# Sheet1.net
KiCad netlist of a schematic drawn in Altium Designer
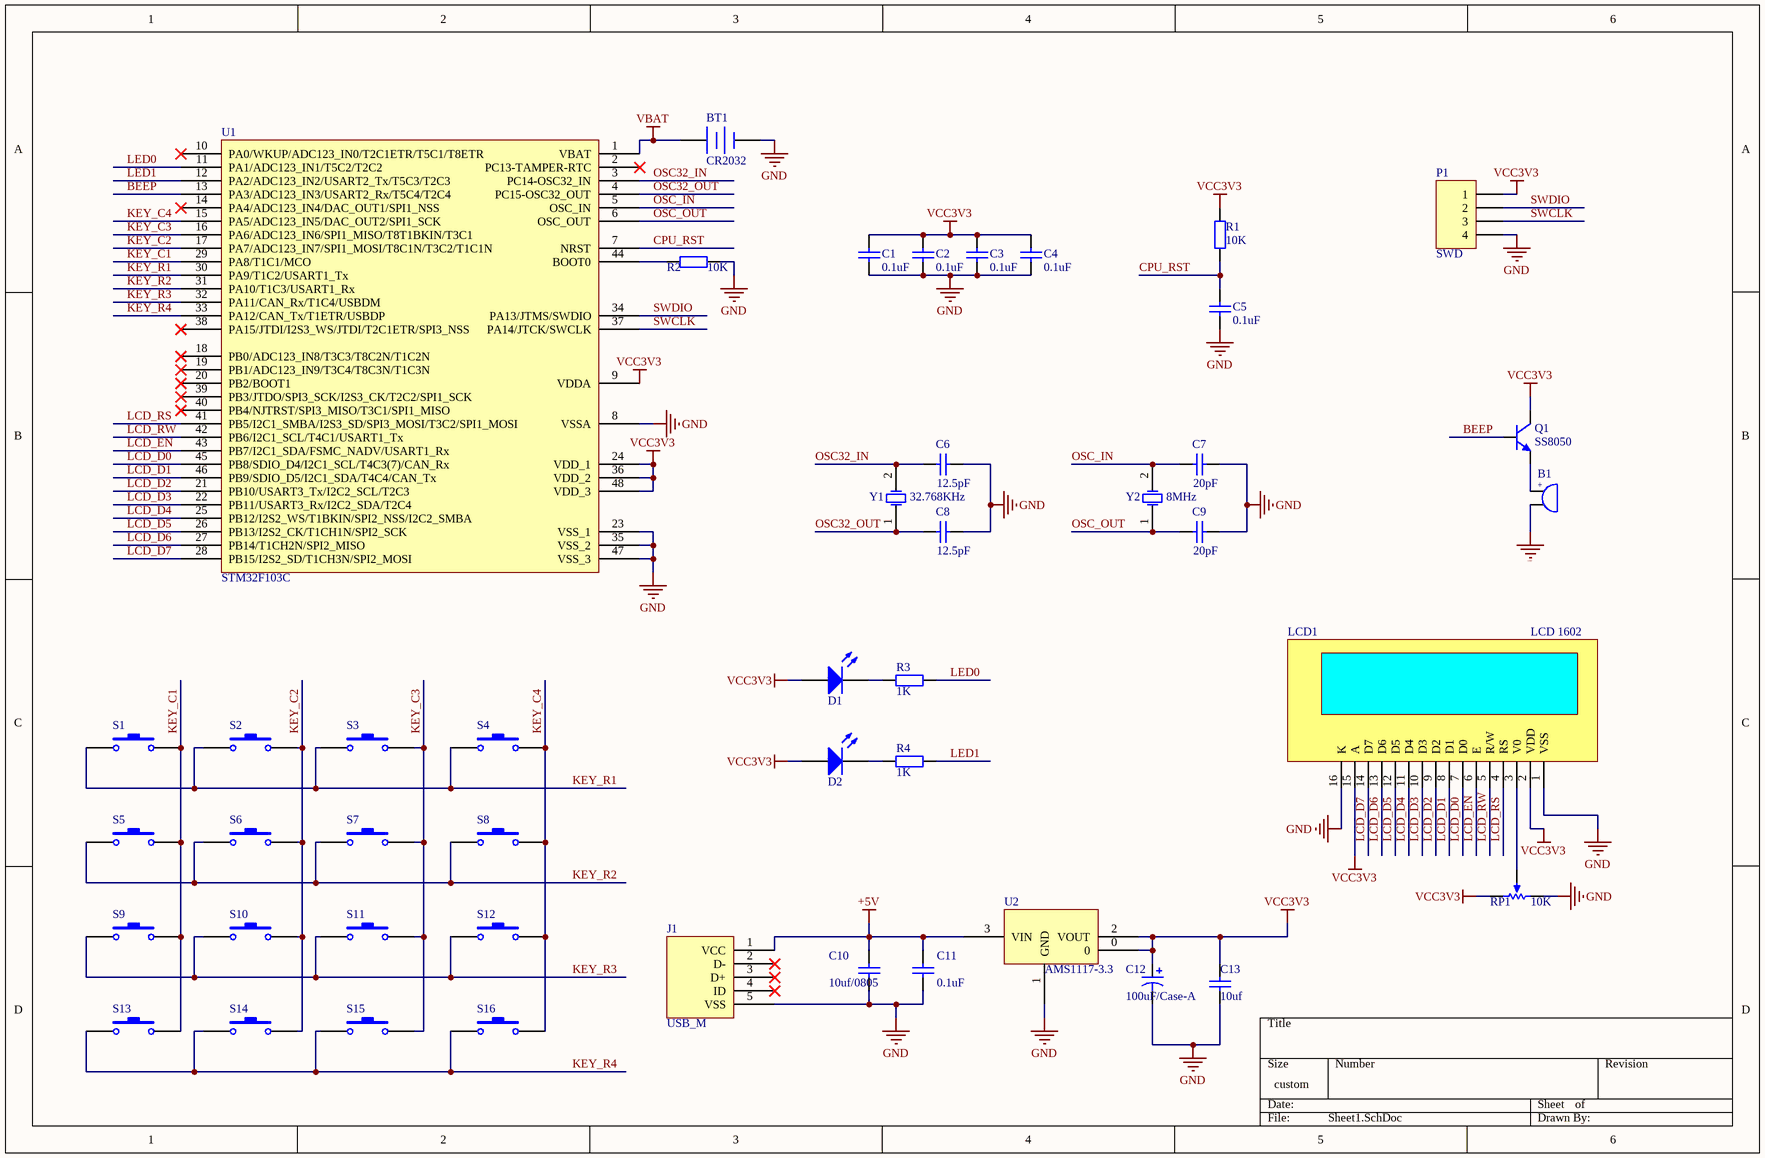
[diagram p0: Sheet1.SchDoc]

(export (version "E")
  (design (tool "Eeschema 10.0.6"))
  (components
    (comp (ref "B1")
      (value "~")
      (footprint "Beep")
      (description "蜂鸣器")
      (fields (field (name "版权归属") "源创客"))
      (libsource (lib "未分类器件") (part "BEEP"))
    )
    (comp (ref "BT1")
      (value "CR2032")
      (footprint "CR1220")
      (description "备份电池")
      (fields (field (name "PUBLISHER") "Altium Limited"))
      (libsource (lib "fszhang") (part "Battery"))
    )
    (comp (ref "C1")
      (value "0.1uF")
      (footprint "C-RAD-0805")
      (description "Capacitor")
      (fields (field (name "PUBLISHER") "Altium Limited"))
      (libsource (lib "Miscellaneous Devices") (part "CAP"))
    )
    (comp (ref "C2")
      (value "0.1uF")
      (footprint "C-RAD-0805")
      (description "Capacitor")
      (fields (field (name "PUBLISHER") "Altium Limited"))
      (libsource (lib "Miscellaneous Devices") (part "CAP"))
    )
    (comp (ref "C3")
      (value "0.1uF")
      (footprint "C-RAD-0805")
      (description "Capacitor")
      (fields (field (name "PUBLISHER") "Altium Limited"))
      (libsource (lib "Miscellaneous Devices") (part "CAP"))
    )
    (comp (ref "C4")
      (value "0.1uF")
      (footprint "C-RAD-0805")
      (description "Capacitor")
      (fields (field (name "PUBLISHER") "Altium Limited"))
      (libsource (lib "Miscellaneous Devices") (part "CAP"))
    )
    (comp (ref "C5")
      (value "0.1uF")
      (footprint "C-RAD-0805")
      (description "无极性电容")
      (fields (field (name "PUBLISHER") "Altium Limited"))
      (libsource (lib "fszhang") (part "Cap"))
    )
    (comp (ref "C6")
      (value "12.5pF")
      (footprint "C-RAD-0805")
      (description "无极性电容")
      (fields (field (name "PUBLISHER") "Altium Limited"))
      (libsource (lib "fszhang") (part "Cap"))
    )
    (comp (ref "C7")
      (value "20pF")
      (footprint "C-RAD-0805")
      (description "无极性电容")
      (fields (field (name "PUBLISHER") "Altium Limited"))
      (libsource (lib "fszhang") (part "Cap"))
    )
    (comp (ref "C8")
      (value "12.5pF")
      (footprint "C-RAD-0805")
      (description "无极性电容")
      (fields (field (name "PUBLISHER") "Altium Limited"))
      (libsource (lib "fszhang") (part "Cap"))
    )
    (comp (ref "C9")
      (value "20pF")
      (footprint "C-RAD-0805")
      (description "无极性电容")
      (fields (field (name "PUBLISHER") "Altium Limited"))
      (libsource (lib "fszhang") (part "Cap"))
    )
    (comp (ref "C10")
      (value "10uf/0805")
      (footprint "C-RAD-0805")
      (description "Capacitor")
      (fields (field (name "Comment") "Cap") (field (name "PUBLISHER") "Altium Limited"))
      (libsource (lib "Miscellaneous Devices") (part "Cap"))
    )
    (comp (ref "C11")
      (value "0.1uF")
      (footprint "C-RAD-0805")
      (description "Capacitor")
      (fields (field (name "Comment") "Cap") (field (name "PUBLISHER") "Altium Limited"))
      (libsource (lib "Miscellaneous Devices") (part "Cap"))
    )
    (comp (ref "C12")
      (value "100uF/Case-A")
      (footprint "CAP-3216")
      (description "Polarized Capacitor (Surface Mount)")
      (fields (field (name "Comment") "Cap Pol3") (field (name "PUBLISHER") "Altium Limited"))
      (libsource (lib "Miscellaneous Devices") (part "Cap Pol3"))
    )
    (comp (ref "C13")
      (value "10uf")
      (footprint "C-RAD-0805")
      (description "Capacitor")
      (fields (field (name "Comment") "Cap") (field (name "PUBLISHER") "Altium Limited"))
      (libsource (lib "Miscellaneous Devices") (part "Cap"))
    )
    (comp (ref "D1")
      (value "LED0")
      (footprint "LED_A2")
      (description "发光二极管")
      (fields (field (name "PUBLISHER") "Altium Limited"))
      (libsource (lib "fszhang") (part "LED0"))
    )
    (comp (ref "D2")
      (value "LED0")
      (footprint "LED_A2")
      (description "发光二极管")
      (fields (field (name "PUBLISHER") "Altium Limited"))
      (libsource (lib "fszhang") (part "LED0"))
    )
    (comp (ref "J1")
      (value "USB_M")
      (footprint "USB_MICRO")
      (description "MicroUSB接口")
      (libsource (lib "fszhang") (part "USB_M"))
    )
    (comp (ref "LCD1")
      (value "LCD 1602")
      (footprint "LCD-1602-ok")
      (fields (field (name "版权归属") "源创客"))
      (libsource (lib "lcd1602") (part "LCD 1602"))
    )
    (comp (ref "P1")
      (value "SWD")
      (footprint "HDR1X4")
      (description "Header, 4-Pin, Right Angle")
      (fields (field (name "PUBLISHER") "Altium Limited"))
      (libsource (lib "Miscellaneous Connectors") (part "Header 4H"))
    )
    (comp (ref "Q1")
      (value "SS8050")
      (footprint "SOT-23")
      (description "高频放大-NPN型")
      (fields (field (name "版权归属") "源创客"))
      (libsource (lib "三极管") (part "8050-DIP"))
    )
    (comp (ref "R1")
      (value "10K")
      (footprint "0805-1")
      (description "Resistor")
      (fields (field (name "PUBLISHER") "Altium Limited"))
      (libsource (lib "") (part "Res2_1"))
    )
    (comp (ref "R2")
      (value "10K")
      (footprint "0805-1")
      (description "Resistor")
      (fields (field (name "PUBLISHER") "Altium Limited"))
      (libsource (lib "") (part "Res2_2"))
    )
    (comp (ref "R3")
      (value "1K")
      (footprint "0805-1")
      (description "Resistor")
      (fields (field (name "PUBLISHER") "Altium Limited"))
      (libsource (lib "Miscellaneous Devices") (part "Res2"))
    )
    (comp (ref "R4")
      (value "1K")
      (footprint "0805-1")
      (description "Resistor")
      (fields (field (name "PUBLISHER") "Altium Limited"))
      (libsource (lib "Miscellaneous Devices") (part "Res2"))
    )
    (comp (ref "RP1")
      (value "10K")
      (footprint "VR_A1")
      (description "精密可调电阻")
      (fields (field (name "Comment") "RPot") (field (name "PUBLISHER") "Altium Limited"))
      (libsource (lib "fszhang") (part "RPot"))
    )
    (comp (ref "S1")
      (value "~")
      (footprint "SW_PB2_A1")
      (description "微动开关")
      (fields (field (name "PUBLISHER") "Altium Limited"))
      (libsource (lib "fszhang") (part "SW-PB"))
    )
    (comp (ref "S2")
      (value "~")
      (footprint "SW_PB2_A1")
      (description "微动开关")
      (fields (field (name "PUBLISHER") "Altium Limited"))
      (libsource (lib "fszhang") (part "SW-PB"))
    )
    (comp (ref "S3")
      (value "~")
      (footprint "SW_PB2_A1")
      (description "微动开关")
      (fields (field (name "PUBLISHER") "Altium Limited"))
      (libsource (lib "fszhang") (part "SW-PB"))
    )
    (comp (ref "S4")
      (value "~")
      (footprint "SW_PB2_A1")
      (description "微动开关")
      (fields (field (name "PUBLISHER") "Altium Limited"))
      (libsource (lib "fszhang") (part "SW-PB"))
    )
    (comp (ref "S5")
      (value "~")
      (footprint "SW_PB2_A1")
      (description "微动开关")
      (fields (field (name "PUBLISHER") "Altium Limited"))
      (libsource (lib "fszhang") (part "SW-PB"))
    )
    (comp (ref "S6")
      (value "~")
      (footprint "SW_PB2_A1")
      (description "微动开关")
      (fields (field (name "PUBLISHER") "Altium Limited"))
      (libsource (lib "fszhang") (part "SW-PB"))
    )
    (comp (ref "S7")
      (value "~")
      (footprint "SW_PB2_A1")
      (description "微动开关")
      (fields (field (name "PUBLISHER") "Altium Limited"))
      (libsource (lib "fszhang") (part "SW-PB"))
    )
    (comp (ref "S8")
      (value "~")
      (footprint "SW_PB2_A1")
      (description "微动开关")
      (fields (field (name "PUBLISHER") "Altium Limited"))
      (libsource (lib "fszhang") (part "SW-PB"))
    )
    (comp (ref "S9")
      (value "~")
      (footprint "SW_PB2_A1")
      (description "微动开关")
      (fields (field (name "PUBLISHER") "Altium Limited"))
      (libsource (lib "fszhang") (part "SW-PB"))
    )
    (comp (ref "S10")
      (value "~")
      (footprint "SW_PB2_A1")
      (description "微动开关")
      (fields (field (name "PUBLISHER") "Altium Limited"))
      (libsource (lib "fszhang") (part "SW-PB"))
    )
    (comp (ref "S11")
      (value "~")
      (footprint "SW_PB2_A1")
      (description "微动开关")
      (fields (field (name "PUBLISHER") "Altium Limited"))
      (libsource (lib "fszhang") (part "SW-PB"))
    )
    (comp (ref "S12")
      (value "~")
      (footprint "SW_PB2_A1")
      (description "微动开关")
      (fields (field (name "PUBLISHER") "Altium Limited"))
      (libsource (lib "fszhang") (part "SW-PB"))
    )
    (comp (ref "S13")
      (value "~")
      (footprint "SW_PB2_A1")
      (description "微动开关")
      (fields (field (name "PUBLISHER") "Altium Limited"))
      (libsource (lib "fszhang") (part "SW-PB"))
    )
    (comp (ref "S14")
      (value "~")
      (footprint "SW_PB2_A1")
      (description "微动开关")
      (fields (field (name "PUBLISHER") "Altium Limited"))
      (libsource (lib "fszhang") (part "SW-PB"))
    )
    (comp (ref "S15")
      (value "~")
      (footprint "SW_PB2_A1")
      (description "微动开关")
      (fields (field (name "PUBLISHER") "Altium Limited"))
      (libsource (lib "fszhang") (part "SW-PB"))
    )
    (comp (ref "S16")
      (value "~")
      (footprint "SW_PB2_A1")
      (description "微动开关")
      (fields (field (name "PUBLISHER") "Altium Limited"))
      (libsource (lib "fszhang") (part "SW-PB"))
    )
    (comp (ref "U1")
      (value "STM32F103C")
      (footprint "LQFP-48_M")
      (description "STM32单片机48引脚")
      (libsource (lib "fszhang") (part "STM32F103C"))
    )
    (comp (ref "U2")
      (value "AMS1117-3.3")
      (footprint "SOT-223")
      (libsource (lib "my_ad_sch_lib") (part "AMS1117-3.3"))
    )
    (comp (ref "Y1")
      (value "32.768KHz")
      (footprint "X-TC15")
      (description "贴片晶振")
      (libsource (lib "Miscellaneous Devices LC") (part "SMD-3215_2P 32.768KHz 20ppm 12.5pF"))
    )
    (comp (ref "Y2")
      (value "8MHz")
      (footprint "X-HC49U")
      (description "贴片晶振")
      (libsource (lib "Miscellaneous Devices LC") (part "SMD-5032_2P 8MHz 20ppm 20pF"))
    )
  )
  (nets
    (net (code "1") (name "+5V") (class "Default")
      (node (ref "C10") (pin "2") (pinfunction "2_2") (pintype "passive"))
      (node (ref "C11") (pin "2") (pinfunction "2_2") (pintype "passive"))
      (node (ref "J1") (pin "1") (pinfunction "VCC_1") (pintype "passive"))
      (node (ref "U2") (pin "3") (pinfunction "VIN_3") (pintype "passive"))
    )
    (net (code "2") (name "/BEEP") (class "Default")
      (node (ref "Q1") (pin "2") (pinfunction "B_2") (pintype "passive"))
      (node (ref "U1") (pin "13") (pinfunction "PA3/ADC123_IN3/USART2_Rx/T5C4/T2C4_13") (pintype "passive"))
    )
    (net (code "3") (name "/CPU_RST") (class "Default")
      (node (ref "C5") (pin "2") (pinfunction "2_2") (pintype "passive"))
      (node (ref "R1") (pin "2") (pinfunction "2_2") (pintype "passive"))
      (node (ref "U1") (pin "7") (pinfunction "NRST_7") (pintype "passive"))
    )
    (net (code "4") (name "/KEY_C1") (class "Default")
      (node (ref "S1") (pin "2") (pinfunction "2_2") (pintype "passive"))
      (node (ref "S13") (pin "2") (pinfunction "2_2") (pintype "passive"))
      (node (ref "S5") (pin "2") (pinfunction "2_2") (pintype "passive"))
      (node (ref "S9") (pin "2") (pinfunction "2_2") (pintype "passive"))
      (node (ref "U1") (pin "29") (pinfunction "PA8/T1C1/MCO_29") (pintype "passive"))
    )
    (net (code "5") (name "/KEY_C2") (class "Default")
      (node (ref "S10") (pin "2") (pinfunction "2_2") (pintype "passive"))
      (node (ref "S14") (pin "2") (pinfunction "2_2") (pintype "passive"))
      (node (ref "S2") (pin "2") (pinfunction "2_2") (pintype "passive"))
      (node (ref "S6") (pin "2") (pinfunction "2_2") (pintype "passive"))
      (node (ref "U1") (pin "17") (pinfunction "PA7/ADC123_IN7/SPI1_MOSI/T8C1N/T3C2/T1C1N_17") (pintype "passive"))
    )
    (net (code "6") (name "/KEY_C3") (class "Default")
      (node (ref "S11") (pin "2") (pinfunction "2_2") (pintype "passive"))
      (node (ref "S15") (pin "2") (pinfunction "2_2") (pintype "passive"))
      (node (ref "S3") (pin "2") (pinfunction "2_2") (pintype "passive"))
      (node (ref "S7") (pin "2") (pinfunction "2_2") (pintype "passive"))
      (node (ref "U1") (pin "16") (pinfunction "PA6/ADC123_IN6/SPI1_MISO/T8T1BKIN/T3C1_16") (pintype "passive"))
    )
    (net (code "7") (name "/KEY_C4") (class "Default")
      (node (ref "S12") (pin "2") (pinfunction "2_2") (pintype "passive"))
      (node (ref "S16") (pin "2") (pinfunction "2_2") (pintype "passive"))
      (node (ref "S4") (pin "2") (pinfunction "2_2") (pintype "passive"))
      (node (ref "S8") (pin "2") (pinfunction "2_2") (pintype "passive"))
      (node (ref "U1") (pin "15") (pinfunction "PA5/ADC123_IN5/DAC_OUT2/SPI1_SCK_15") (pintype "passive"))
    )
    (net (code "8") (name "/KEY_R1") (class "Default")
      (node (ref "S1") (pin "1") (pinfunction "1_1") (pintype "passive"))
      (node (ref "S2") (pin "1") (pinfunction "1_1") (pintype "passive"))
      (node (ref "S3") (pin "1") (pinfunction "1_1") (pintype "passive"))
      (node (ref "S4") (pin "1") (pinfunction "1_1") (pintype "passive"))
      (node (ref "U1") (pin "30") (pinfunction "PA9/T1C2/USART1_Tx_30") (pintype "passive"))
    )
    (net (code "9") (name "/KEY_R2") (class "Default")
      (node (ref "S5") (pin "1") (pinfunction "1_1") (pintype "passive"))
      (node (ref "S6") (pin "1") (pinfunction "1_1") (pintype "passive"))
      (node (ref "S7") (pin "1") (pinfunction "1_1") (pintype "passive"))
      (node (ref "S8") (pin "1") (pinfunction "1_1") (pintype "passive"))
      (node (ref "U1") (pin "31") (pinfunction "PA10/T1C3/USART1_Rx_31") (pintype "passive"))
    )
    (net (code "10") (name "/KEY_R3") (class "Default")
      (node (ref "S10") (pin "1") (pinfunction "1_1") (pintype "passive"))
      (node (ref "S11") (pin "1") (pinfunction "1_1") (pintype "passive"))
      (node (ref "S12") (pin "1") (pinfunction "1_1") (pintype "passive"))
      (node (ref "S9") (pin "1") (pinfunction "1_1") (pintype "passive"))
      (node (ref "U1") (pin "32") (pinfunction "PA11/CAN_Rx/T1C4/USBDM_32") (pintype "passive"))
    )
    (net (code "11") (name "/KEY_R4") (class "Default")
      (node (ref "S13") (pin "1") (pinfunction "1_1") (pintype "passive"))
      (node (ref "S14") (pin "1") (pinfunction "1_1") (pintype "passive"))
      (node (ref "S15") (pin "1") (pinfunction "1_1") (pintype "passive"))
      (node (ref "S16") (pin "1") (pinfunction "1_1") (pintype "passive"))
      (node (ref "U1") (pin "33") (pinfunction "PA12/CAN_Tx/T1ETR/USBDP_33") (pintype "passive"))
    )
    (net (code "12") (name "/LCD_D0") (class "Default")
      (node (ref "LCD1") (pin "7") (pinfunction "D0_7") (pintype "passive"))
      (node (ref "U1") (pin "45") (pinfunction "PB8/SDIO_D4/I2C1_SCL/T4C3(7)/CAN_Rx_45") (pintype "passive"))
    )
    (net (code "13") (name "/LCD_D1") (class "Default")
      (node (ref "LCD1") (pin "8") (pinfunction "D1_8") (pintype "passive"))
      (node (ref "U1") (pin "46") (pinfunction "PB9/SDIO_D5/I2C1_SDA/T4C4/CAN_Tx_46") (pintype "passive"))
    )
    (net (code "14") (name "/LCD_D2") (class "Default")
      (node (ref "LCD1") (pin "9") (pinfunction "D2_9") (pintype "passive"))
      (node (ref "U1") (pin "21") (pinfunction "PB10/USART3_Tx/I2C2_SCL/T2C3_21") (pintype "passive"))
    )
    (net (code "15") (name "/LCD_D3") (class "Default")
      (node (ref "LCD1") (pin "10") (pinfunction "D3_10") (pintype "passive"))
      (node (ref "U1") (pin "22") (pinfunction "PB11/USART3_Rx/I2C2_SDA/T2C4_22") (pintype "passive"))
    )
    (net (code "16") (name "/LCD_D4") (class "Default")
      (node (ref "LCD1") (pin "11") (pinfunction "D4_11") (pintype "passive"))
      (node (ref "U1") (pin "25") (pinfunction "PB12/I2S2_WS/T1BKIN/SPI2_NSS/I2C2_SMBA_25") (pintype "passive"))
    )
    (net (code "17") (name "/LCD_D5") (class "Default")
      (node (ref "LCD1") (pin "12") (pinfunction "D5_12") (pintype "passive"))
      (node (ref "U1") (pin "26") (pinfunction "PB13/I2S2_CK/T1CH1N/SPI2_SCK_26") (pintype "passive"))
    )
    (net (code "18") (name "/LCD_D6") (class "Default")
      (node (ref "LCD1") (pin "13") (pinfunction "D6_13") (pintype "passive"))
      (node (ref "U1") (pin "27") (pinfunction "PB14/T1CH2N/SPI2_MISO_27") (pintype "passive"))
    )
    (net (code "19") (name "/LCD_D7") (class "Default")
      (node (ref "LCD1") (pin "14") (pinfunction "D7_14") (pintype "passive"))
      (node (ref "U1") (pin "28") (pinfunction "PB15/I2S2_SD/T1CH3N/SPI2_MOSI_28") (pintype "passive"))
    )
    (net (code "20") (name "/LCD_EN") (class "Default")
      (node (ref "LCD1") (pin "6") (pinfunction "E_6") (pintype "passive"))
      (node (ref "U1") (pin "43") (pinfunction "PB7/I2C1_SDA/FSMC_NADV/USART1_Rx_43") (pintype "passive"))
    )
    (net (code "21") (name "/LCD_RS") (class "Default")
      (node (ref "LCD1") (pin "4") (pinfunction "RS_4") (pintype "passive"))
      (node (ref "U1") (pin "41") (pinfunction "PB5/I2C1_SMBA/I2S3_SD/SPI3_MOSI/T3C2/SPI1_MOSI_41") (pintype "passive"))
    )
    (net (code "22") (name "/LCD_RW") (class "Default")
      (node (ref "LCD1") (pin "5") (pinfunction "R/W_5") (pintype "passive"))
      (node (ref "U1") (pin "42") (pinfunction "PB6/I2C1_SCL/T4C1/USART1_Tx_42") (pintype "passive"))
    )
    (net (code "23") (name "/LED0") (class "Default")
      (node (ref "R3") (pin "1") (pinfunction "1_1") (pintype "passive"))
      (node (ref "U1") (pin "11") (pinfunction "PA1/ADC123_IN1/T5C2/T2C2_11") (pintype "passive"))
    )
    (net (code "24") (name "/LED1") (class "Default")
      (node (ref "R4") (pin "1") (pinfunction "1_1") (pintype "passive"))
      (node (ref "U1") (pin "12") (pinfunction "PA2/ADC123_IN2/USART2_Tx/T5C3/T2C3_12") (pintype "passive"))
    )
    (net (code "25") (name "/OSC32_IN") (class "Default")
      (node (ref "C6") (pin "1") (pinfunction "1_1") (pintype "passive"))
      (node (ref "U1") (pin "3") (pinfunction "PC14-OSC32_IN_3") (pintype "passive"))
      (node (ref "Y1") (pin "2") (pinfunction "OSC2_2") (pintype "passive"))
    )
    (net (code "26") (name "/OSC32_OUT") (class "Default")
      (node (ref "C8") (pin "1") (pinfunction "1_1") (pintype "passive"))
      (node (ref "U1") (pin "4") (pinfunction "PC15-OSC32_OUT_4") (pintype "passive"))
      (node (ref "Y1") (pin "1") (pinfunction "OSC1_1") (pintype "passive"))
    )
    (net (code "27") (name "/OSC_IN") (class "Default")
      (node (ref "C7") (pin "1") (pinfunction "1_1") (pintype "passive"))
      (node (ref "U1") (pin "5") (pinfunction "OSC_IN_5") (pintype "passive"))
      (node (ref "Y2") (pin "2") (pinfunction "OSC2_2") (pintype "passive"))
    )
    (net (code "28") (name "/OSC_OUT") (class "Default")
      (node (ref "C9") (pin "1") (pinfunction "1_1") (pintype "passive"))
      (node (ref "U1") (pin "6") (pinfunction "OSC_OUT_6") (pintype "passive"))
      (node (ref "Y2") (pin "1") (pinfunction "OSC1_1") (pintype "passive"))
    )
    (net (code "29") (name "/SWCLK") (class "Default")
      (node (ref "P1") (pin "3") (pinfunction "3_3") (pintype "passive"))
      (node (ref "U1") (pin "37") (pinfunction "PA14/JTCK/SWCLK_37") (pintype "passive"))
    )
    (net (code "30") (name "/SWDIO") (class "Default")
      (node (ref "P1") (pin "2") (pinfunction "2_2") (pintype "passive"))
      (node (ref "U1") (pin "34") (pinfunction "PA13/JTMS/SWDIO_34") (pintype "passive"))
    )
    (net (code "31") (name "GND") (class "Default")
      (node (ref "B1") (pin "2") (pinfunction "2_2") (pintype "passive"))
      (node (ref "BT1") (pin "2") (pinfunction "-_2") (pintype "passive"))
      (node (ref "C1") (pin "2") (pinfunction "2_2") (pintype "passive"))
      (node (ref "C10") (pin "1") (pinfunction "1_1") (pintype "passive"))
      (node (ref "C11") (pin "1") (pinfunction "1_1") (pintype "passive"))
      (node (ref "C12") (pin "2") (pinfunction "2_2") (pintype "passive"))
      (node (ref "C13") (pin "1") (pinfunction "1_1") (pintype "passive"))
      (node (ref "C2") (pin "2") (pinfunction "2_2") (pintype "passive"))
      (node (ref "C3") (pin "2") (pinfunction "2_2") (pintype "passive"))
      (node (ref "C4") (pin "2") (pinfunction "2_2") (pintype "passive"))
      (node (ref "C5") (pin "1") (pinfunction "1_1") (pintype "passive"))
      (node (ref "C6") (pin "2") (pinfunction "2_2") (pintype "passive"))
      (node (ref "C7") (pin "2") (pinfunction "2_2") (pintype "passive"))
      (node (ref "C8") (pin "2") (pinfunction "2_2") (pintype "passive"))
      (node (ref "C9") (pin "2") (pinfunction "2_2") (pintype "passive"))
      (node (ref "J1") (pin "5") (pinfunction "VSS_5") (pintype "passive"))
      (node (ref "LCD1") (pin "1") (pinfunction "VSS_1") (pintype "passive"))
      (node (ref "LCD1") (pin "16") (pinfunction "K_16") (pintype "passive"))
      (node (ref "P1") (pin "4") (pinfunction "4_4") (pintype "passive"))
      (node (ref "R2") (pin "2") (pinfunction "2_2") (pintype "passive"))
      (node (ref "RP1") (pin "1") (pinfunction "TOP_1") (pintype "passive"))
      (node (ref "U1") (pin "23") (pinfunction "VSS_1_23") (pintype "passive"))
      (node (ref "U1") (pin "35") (pinfunction "VSS_2_35") (pintype "passive"))
      (node (ref "U1") (pin "47") (pinfunction "VSS_3_47") (pintype "passive"))
      (node (ref "U1") (pin "8") (pinfunction "VSSA_8") (pintype "passive"))
      (node (ref "U2") (pin "1") (pinfunction "GND_1") (pintype "passive"))
    )
    (net (code "32") (name "Net-(D1-K)") (class "Default")
      (node (ref "D1") (pin "2") (pinfunction "K_2") (pintype "passive"))
      (node (ref "R3") (pin "2") (pinfunction "2_2") (pintype "passive"))
    )
    (net (code "33") (name "Net-(D2-K)") (class "Default")
      (node (ref "D2") (pin "2") (pinfunction "K_2") (pintype "passive"))
      (node (ref "R4") (pin "2") (pinfunction "2_2") (pintype "passive"))
    )
    (net (code "34") (name "Net-(LCD1-V0)") (class "Default")
      (node (ref "LCD1") (pin "3") (pinfunction "V0_3") (pintype "passive"))
      (node (ref "RP1") (pin "2") (pinfunction "TAP_2") (pintype "passive"))
    )
    (net (code "35") (name "Net-(Q1-E)") (class "Default")
      (node (ref "B1") (pin "1") (pinfunction "1_1") (pintype "passive"))
      (node (ref "Q1") (pin "1") (pinfunction "E_1") (pintype "passive"))
    )
    (net (code "36") (name "Net-(U1-BOOT0)") (class "Default")
      (node (ref "R2") (pin "1") (pinfunction "1_1") (pintype "passive"))
      (node (ref "U1") (pin "44") (pinfunction "BOOT0_44") (pintype "passive"))
    )
    (net (code "37") (name "VBAT") (class "Default")
      (node (ref "BT1") (pin "1") (pinfunction "+_1") (pintype "passive"))
      (node (ref "U1") (pin "1") (pinfunction "VBAT_1") (pintype "passive"))
    )
    (net (code "38") (name "VCC3V3") (class "Default")
      (node (ref "C1") (pin "1") (pinfunction "1_1") (pintype "passive"))
      (node (ref "C12") (pin "1") (pinfunction "1_1") (pintype "passive"))
      (node (ref "C13") (pin "2") (pinfunction "2_2") (pintype "passive"))
      (node (ref "C2") (pin "1") (pinfunction "1_1") (pintype "passive"))
      (node (ref "C3") (pin "1") (pinfunction "1_1") (pintype "passive"))
      (node (ref "C4") (pin "1") (pinfunction "1_1") (pintype "passive"))
      (node (ref "D1") (pin "1") (pinfunction "A_1") (pintype "passive"))
      (node (ref "D2") (pin "1") (pinfunction "A_1") (pintype "passive"))
      (node (ref "LCD1") (pin "15") (pinfunction "A_15") (pintype "passive"))
      (node (ref "LCD1") (pin "2") (pinfunction "VDD_2") (pintype "passive"))
      (node (ref "P1") (pin "1") (pinfunction "1_1") (pintype "passive"))
      (node (ref "Q1") (pin "3") (pinfunction "C_3") (pintype "passive"))
      (node (ref "R1") (pin "1") (pinfunction "1_1") (pintype "passive"))
      (node (ref "RP1") (pin "3") (pinfunction "BOT_3") (pintype "passive"))
      (node (ref "U1") (pin "24") (pinfunction "VDD_1_24") (pintype "passive"))
      (node (ref "U1") (pin "36") (pinfunction "VDD_2_36") (pintype "passive"))
      (node (ref "U1") (pin "48") (pinfunction "VDD_3_48") (pintype "passive"))
      (node (ref "U1") (pin "9") (pinfunction "VDDA_9") (pintype "passive"))
      (node (ref "U2") (pin "0") (pinfunction "0_0") (pintype "passive"))
      (node (ref "U2") (pin "2") (pinfunction "VOUT_2") (pintype "passive"))
    )
    (net (code "39") (name "unconnected-(J1-D+-Pad3)") (class "Default")
      (node (ref "J1") (pin "3") (pinfunction "D+_3") (pintype "passive+no_connect"))
    )
    (net (code "40") (name "unconnected-(J1-D--Pad2)") (class "Default")
      (node (ref "J1") (pin "2") (pinfunction "D-_2") (pintype "passive+no_connect"))
    )
    (net (code "41") (name "unconnected-(J1-ID-Pad4)") (class "Default")
      (node (ref "J1") (pin "4") (pinfunction "ID_4") (pintype "passive+no_connect"))
    )
    (net (code "42") (name "unconnected-(U1-PA0{slash}WKUP{slash}ADC123_IN0{slash}T2C1ETR{slash}T5C1{slash}T8ETR-Pad10)") (class "Default")
      (node (ref "U1") (pin "10") (pinfunction "PA0/WKUP/ADC123_IN0/T2C1ETR/T5C1/T8ETR_10") (pintype "passive+no_connect"))
    )
    (net (code "43") (name "unconnected-(U1-PA4{slash}ADC123_IN4{slash}DAC_OUT1{slash}SPI1_NSS-Pad14)") (class "Default")
      (node (ref "U1") (pin "14") (pinfunction "PA4/ADC123_IN4/DAC_OUT1/SPI1_NSS_14") (pintype "passive+no_connect"))
    )
    (net (code "44") (name "unconnected-(U1-PA15{slash}JTDI{slash}I2S3_WS{slash}JTDI{slash}T2C1ETR{slash}SPI3_NSS-Pad38)") (class "Default")
      (node (ref "U1") (pin "38") (pinfunction "PA15/JTDI/I2S3_WS/JTDI/T2C1ETR/SPI3_NSS_38") (pintype "passive+no_connect"))
    )
    (net (code "45") (name "unconnected-(U1-PB0{slash}ADC123_IN8{slash}T3C3{slash}T8C2N{slash}T1C2N-Pad18)") (class "Default")
      (node (ref "U1") (pin "18") (pinfunction "PB0/ADC123_IN8/T3C3/T8C2N/T1C2N_18") (pintype "passive+no_connect"))
    )
    (net (code "46") (name "unconnected-(U1-PB1{slash}ADC123_IN9{slash}T3C4{slash}T8C3N{slash}T1C3N-Pad19)") (class "Default")
      (node (ref "U1") (pin "19") (pinfunction "PB1/ADC123_IN9/T3C4/T8C3N/T1C3N_19") (pintype "passive+no_connect"))
    )
    (net (code "47") (name "unconnected-(U1-PB2{slash}BOOT1-Pad20)") (class "Default")
      (node (ref "U1") (pin "20") (pinfunction "PB2/BOOT1_20") (pintype "passive+no_connect"))
    )
    (net (code "48") (name "unconnected-(U1-PB3{slash}JTDO{slash}SPI3_SCK{slash}I2S3_CK{slash}T2C2{slash}SPI1_SCK-Pad39)") (class "Default")
      (node (ref "U1") (pin "39") (pinfunction "PB3/JTDO/SPI3_SCK/I2S3_CK/T2C2/SPI1_SCK_39") (pintype "passive+no_connect"))
    )
    (net (code "49") (name "unconnected-(U1-PB4{slash}NJTRST{slash}SPI3_MISO{slash}T3C1{slash}SPI1_MISO-Pad40)") (class "Default")
      (node (ref "U1") (pin "40") (pinfunction "PB4/NJTRST/SPI3_MISO/T3C1/SPI1_MISO_40") (pintype "passive+no_connect"))
    )
    (net (code "50") (name "unconnected-(U1-PC13-TAMPER-RTC-Pad2)") (class "Default")
      (node (ref "U1") (pin "2") (pinfunction "PC13-TAMPER-RTC_2") (pintype "passive+no_connect"))
    )
  )
)
